# Communications.net
KiCad netlist of a schematic drawn in Altium Designer
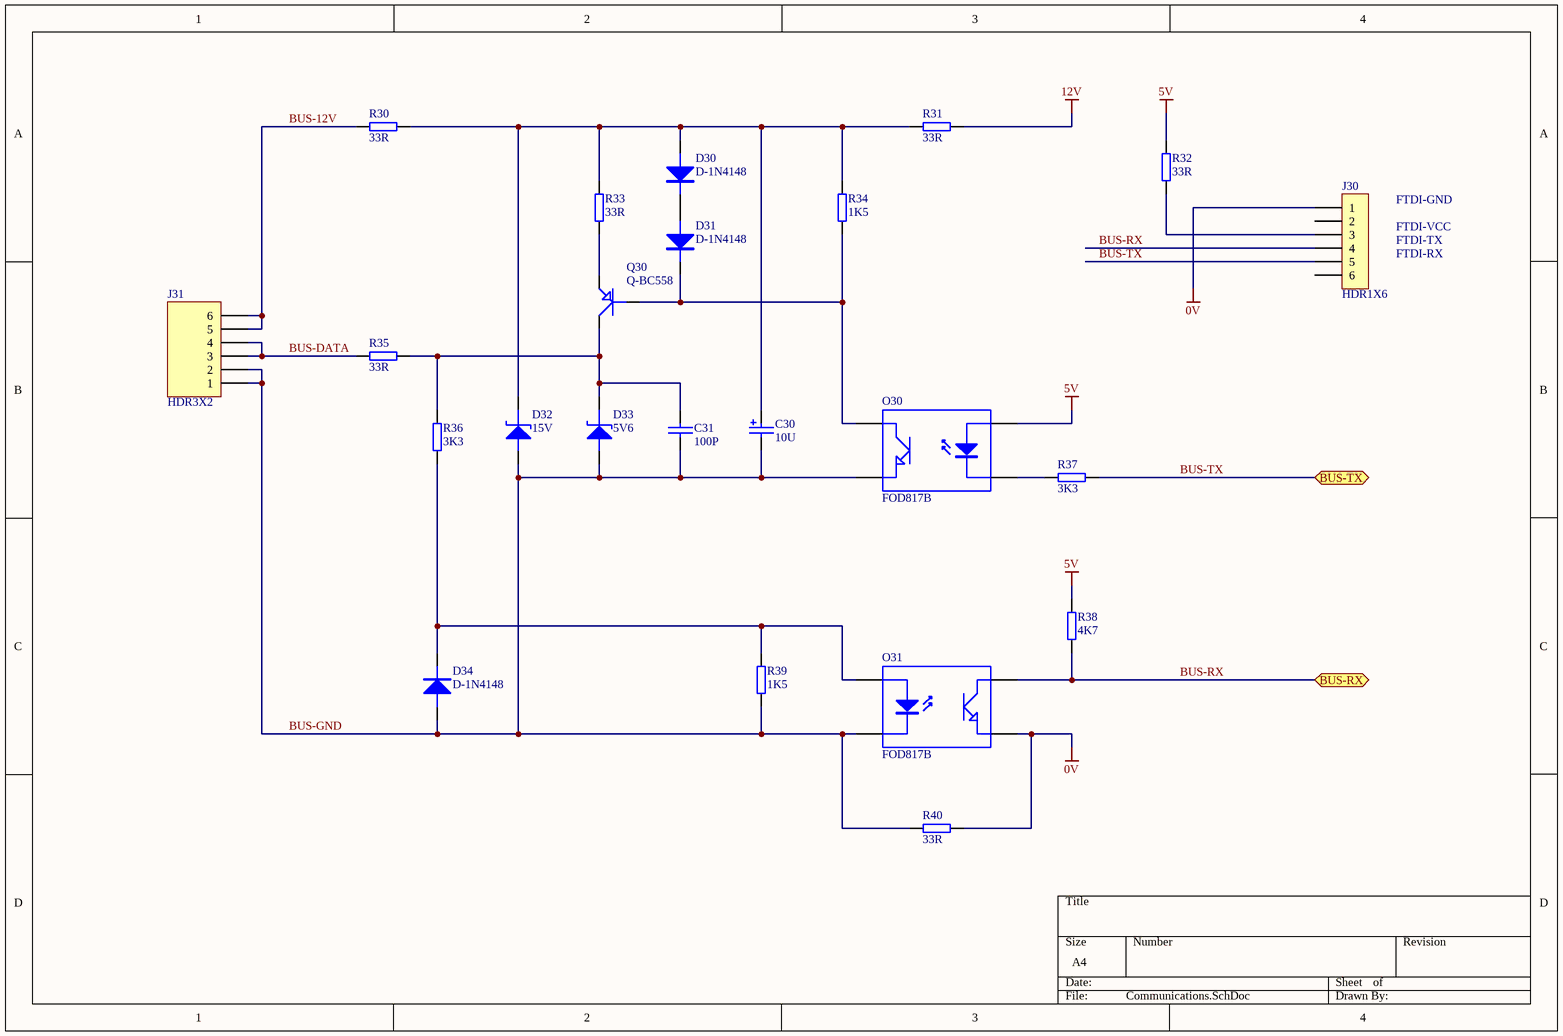
[diagram p0: Communications.SchDoc]

(export (version "E")
  (design (tool "Eeschema 10.0.6"))
  (components
    (comp (ref "C30")
      (value "10U")
      (footprint "RADIAL02P")
      (description "CAP")
      (libsource (lib "SSR") (part "C-A10U"))
    )
    (comp (ref "C31")
      (value "100P")
      (footprint "AXIAL02")
      (description "CAPACITOR")
      (libsource (lib "SSR") (part "C-B100P"))
    )
    (comp (ref "D30")
      (value "D-1N4148")
      (footprint "DO35S")
      (description "1N4148")
      (libsource (lib "SSR") (part "D-1N4148"))
    )
    (comp (ref "D31")
      (value "D-1N4148")
      (footprint "DO35S")
      (description "1N4148")
      (libsource (lib "SSR") (part "D-1N4148"))
    )
    (comp (ref "D32")
      (value "15V")
      (footprint "DO35S")
      (description "ZENER DIODE")
      (libsource (lib "SSR") (part "D-BZX79-15"))
    )
    (comp (ref "D33")
      (value "5V6")
      (footprint "DO35S")
      (description "ZENER DIODE")
      (libsource (lib "SSR") (part "D-BZX79-5V6"))
    )
    (comp (ref "D34")
      (value "D-1N4148")
      (footprint "DO35S")
      (description "1N4148")
      (libsource (lib "SSR") (part "D-1N4148"))
    )
    (comp (ref "J30")
      (value "HDR1X6")
      (footprint "HDR6X1")
      (description "CONNECTOR")
      (libsource (lib "SSR") (part "J-HDR1X6"))
    )
    (comp (ref "J31")
      (value "HDR3X2")
      (footprint "HDR3X2")
      (description "CONNECTOR")
      (libsource (lib "SSR") (part "J-HDR3X2A"))
    )
    (comp (ref "O30")
      (value "FOD817B")
      (footprint "DIP4")
      (description "OPTO ISOLATOR")
      (libsource (lib "") (part "O-FOD817B_1"))
    )
    (comp (ref "O31")
      (value "FOD817B")
      (footprint "DIP4")
      (description "OPTO ISOLATOR")
      (libsource (lib "SSR") (part "O-FOD817B"))
    )
    (comp (ref "Q30")
      (value "Q-BC558")
      (footprint "TO92")
      (description "BC558")
      (libsource (lib "SSR") (part "Q-BC558"))
    )
    (comp (ref "R30")
      (value "33R")
      (footprint "AXIAL04")
      (description "RESISTOR")
      (libsource (lib "SSR") (part "R-A33R"))
    )
    (comp (ref "R31")
      (value "33R")
      (footprint "AXIAL04")
      (description "RESISTOR")
      (libsource (lib "SSR") (part "R-A33R"))
    )
    (comp (ref "R32")
      (value "33R")
      (footprint "AXIAL04")
      (description "RESISTOR")
      (libsource (lib "SSR") (part "R-A33R"))
    )
    (comp (ref "R33")
      (value "33R")
      (footprint "AXIAL04")
      (description "RESISTOR")
      (libsource (lib "SSR") (part "R-A33R"))
    )
    (comp (ref "R34")
      (value "1K5")
      (footprint "AXIAL04")
      (description "RESISTOR")
      (libsource (lib "SSR") (part "R-A1K5"))
    )
    (comp (ref "R35")
      (value "33R")
      (footprint "AXIAL04")
      (description "RESISTOR")
      (libsource (lib "SSR") (part "R-A33R"))
    )
    (comp (ref "R36")
      (value "3K3")
      (footprint "AXIAL04")
      (description "RESISTOR")
      (libsource (lib "SSR") (part "R-A3K3"))
    )
    (comp (ref "R37")
      (value "3K3")
      (footprint "AXIAL04")
      (description "RESISTOR")
      (libsource (lib "SSR") (part "R-A3K3"))
    )
    (comp (ref "R38")
      (value "4K7")
      (footprint "AXIAL04")
      (description "RESISTOR")
      (libsource (lib "SSR") (part "R-A4K7"))
    )
    (comp (ref "R39")
      (value "1K5")
      (footprint "AXIAL04")
      (description "RESISTOR")
      (libsource (lib "SSR") (part "R-A1K5"))
    )
    (comp (ref "R40")
      (value "33R")
      (footprint "AXIAL04")
      (description "RESISTOR")
      (libsource (lib "SSR") (part "R-A33R"))
    )
  )
  (nets
    (net (code "1") (name "/BUS-12V") (class "Default")
      (node (ref "J31") (pin "5") (pinfunction "5_5") (pintype "passive"))
      (node (ref "J31") (pin "6") (pinfunction "6_6") (pintype "passive"))
      (node (ref "R30") (pin "1") (pinfunction "1_1") (pintype "passive"))
    )
    (net (code "2") (name "/BUS-DATA") (class "Default")
      (node (ref "J31") (pin "3") (pinfunction "3_3") (pintype "passive"))
      (node (ref "J31") (pin "4") (pinfunction "4_4") (pintype "passive"))
      (node (ref "R35") (pin "1") (pinfunction "1_1") (pintype "passive"))
    )
    (net (code "3") (name "/BUS-GND") (class "Default")
      (node (ref "C30") (pin "2") (pinfunction "2_2") (pintype "passive"))
      (node (ref "C31") (pin "2") (pinfunction "2_2") (pintype "passive"))
      (node (ref "D32") (pin "1") (pinfunction "A_1") (pintype "passive"))
      (node (ref "D33") (pin "1") (pinfunction "A_1") (pintype "passive"))
      (node (ref "D34") (pin "1") (pinfunction "A_1") (pintype "passive"))
      (node (ref "J31") (pin "1") (pinfunction "1_1") (pintype "passive"))
      (node (ref "J31") (pin "2") (pinfunction "2_2") (pintype "passive"))
      (node (ref "O30") (pin "3") (pinfunction "E_3") (pintype "passive"))
      (node (ref "O31") (pin "2") (pinfunction "K_2") (pintype "passive"))
      (node (ref "R39") (pin "1") (pinfunction "1_1") (pintype "passive"))
      (node (ref "R40") (pin "1") (pinfunction "1_1") (pintype "passive"))
    )
    (net (code "4") (name "/BUS-RX") (class "Default")
      (node (ref "J30") (pin "4") (pinfunction "4_4") (pintype "passive"))
      (node (ref "O31") (pin "4") (pinfunction "C_4") (pintype "passive"))
      (node (ref "R38") (pin "1") (pinfunction "1_1") (pintype "passive"))
    )
    (net (code "5") (name "/BUS-TX") (class "Default")
      (node (ref "J30") (pin "5") (pinfunction "5_5") (pintype "passive"))
      (node (ref "R37") (pin "1") (pinfunction "1_1") (pintype "passive"))
    )
    (net (code "6") (name "0V") (class "Default")
      (node (ref "J30") (pin "1") (pinfunction "1_1") (pintype "passive"))
      (node (ref "O31") (pin "3") (pinfunction "E_3") (pintype "passive"))
      (node (ref "R40") (pin "2") (pinfunction "2_2") (pintype "passive"))
    )
    (net (code "7") (name "5V") (class "Default")
      (node (ref "O30") (pin "1") (pinfunction "A_1") (pintype "passive"))
      (node (ref "R32") (pin "2") (pinfunction "2_2") (pintype "passive"))
      (node (ref "R38") (pin "2") (pinfunction "2_2") (pintype "passive"))
    )
    (net (code "8") (name "12V") (class "Default")
      (node (ref "R31") (pin "2") (pinfunction "2_2") (pintype "passive"))
    )
    (net (code "9") (name "Net-(D30-A)") (class "Default")
      (node (ref "C30") (pin "1") (pinfunction "1_1") (pintype "passive"))
      (node (ref "D30") (pin "1") (pinfunction "A_1") (pintype "passive"))
      (node (ref "D32") (pin "2") (pinfunction "K_2") (pintype "passive"))
      (node (ref "R30") (pin "2") (pinfunction "2_2") (pintype "passive"))
      (node (ref "R31") (pin "1") (pinfunction "1_1") (pintype "passive"))
      (node (ref "R33") (pin "2") (pinfunction "2_2") (pintype "passive"))
      (node (ref "R34") (pin "2") (pinfunction "2_2") (pintype "passive"))
    )
    (net (code "10") (name "Net-(D30-K)") (class "Default")
      (node (ref "D30") (pin "2") (pinfunction "K_2") (pintype "passive"))
      (node (ref "D31") (pin "1") (pinfunction "A_1") (pintype "passive"))
    )
    (net (code "11") (name "Net-(D31-K)") (class "Default")
      (node (ref "D31") (pin "2") (pinfunction "K_2") (pintype "passive"))
      (node (ref "O30") (pin "4") (pinfunction "C_4") (pintype "passive"))
      (node (ref "Q30") (pin "2") (pinfunction "B_2") (pintype "passive"))
      (node (ref "R34") (pin "1") (pinfunction "1_1") (pintype "passive"))
    )
    (net (code "12") (name "Net-(D33-K)") (class "Default")
      (node (ref "C31") (pin "1") (pinfunction "1_1") (pintype "passive"))
      (node (ref "D33") (pin "2") (pinfunction "K_2") (pintype "passive"))
      (node (ref "Q30") (pin "3") (pinfunction "C_3") (pintype "passive"))
      (node (ref "R35") (pin "2") (pinfunction "2_2") (pintype "passive"))
      (node (ref "R36") (pin "2") (pinfunction "2_2") (pintype "passive"))
    )
    (net (code "13") (name "Net-(D34-K)") (class "Default")
      (node (ref "D34") (pin "2") (pinfunction "K_2") (pintype "passive"))
      (node (ref "O31") (pin "1") (pinfunction "A_1") (pintype "passive"))
      (node (ref "R36") (pin "1") (pinfunction "1_1") (pintype "passive"))
      (node (ref "R39") (pin "2") (pinfunction "2_2") (pintype "passive"))
    )
    (net (code "14") (name "Net-(J30-Pad3)") (class "Default")
      (node (ref "J30") (pin "3") (pinfunction "3_3") (pintype "passive"))
      (node (ref "R32") (pin "1") (pinfunction "1_1") (pintype "passive"))
    )
    (net (code "15") (name "Net-(O30-K)") (class "Default")
      (node (ref "O30") (pin "2") (pinfunction "K_2") (pintype "passive"))
      (node (ref "R37") (pin "2") (pinfunction "2_2") (pintype "passive"))
    )
    (net (code "16") (name "Net-(Q30-E)") (class "Default")
      (node (ref "Q30") (pin "1") (pinfunction "E_1") (pintype "passive"))
      (node (ref "R33") (pin "1") (pinfunction "1_1") (pintype "passive"))
    )
    (net (code "17") (name "unconnected-(J30-Pad2)") (class "Default")
      (node (ref "J30") (pin "2") (pinfunction "2_2") (pintype "passive"))
    )
    (net (code "18") (name "unconnected-(J30-Pad6)") (class "Default")
      (node (ref "J30") (pin "6") (pinfunction "6_6") (pintype "passive"))
    )
  )
)
